# SerialChiller.net
KiCad netlist of a schematic drawn in EAGLE
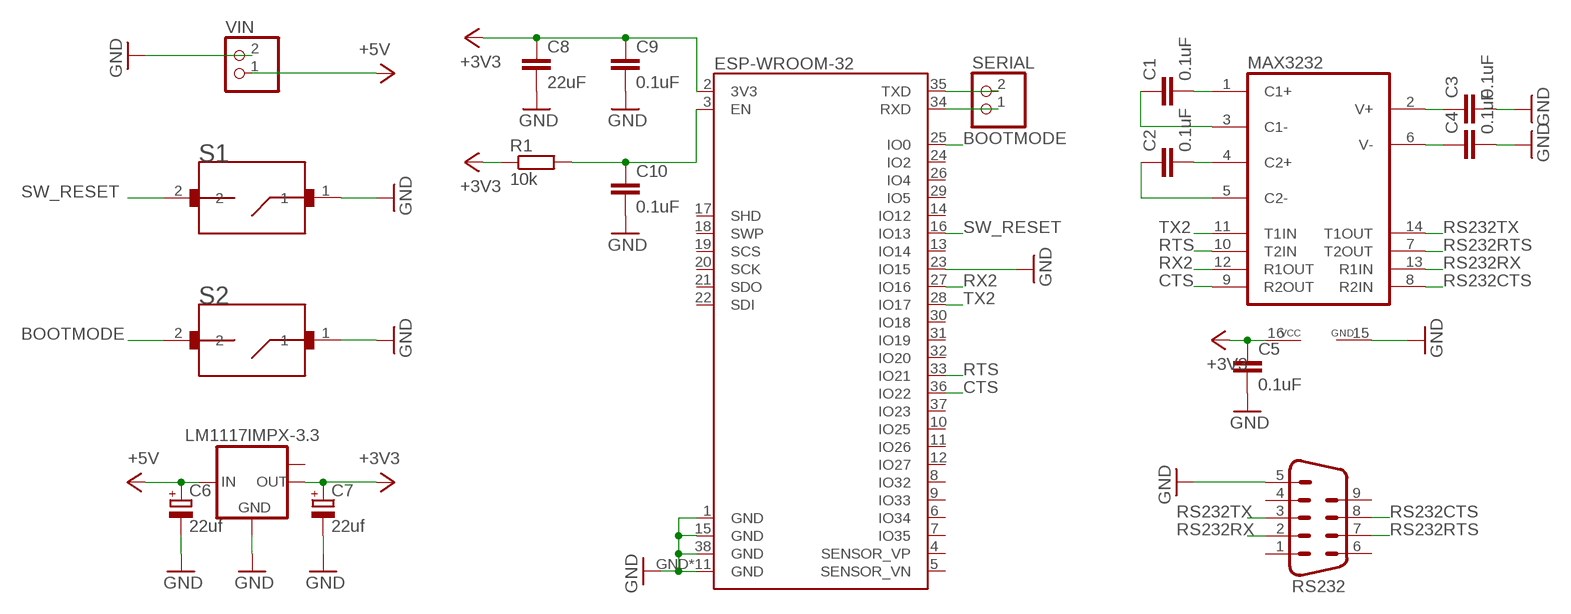
[diagram p0: schematic, sheet 1]

(export (version "E")
  (design (tool "Eeschema 10.0.6"))
  (components
    (comp (ref "C1")
      (value "0.1uF")
      (footprint "eagle-import:C0603")
      (libsource (lib "eagle-import") (part "C-EUC0603"))
    )
    (comp (ref "C2")
      (value "0.1uF")
      (footprint "eagle-import:C0603")
      (libsource (lib "eagle-import") (part "C-EUC0603"))
    )
    (comp (ref "C3")
      (value "0.1uF")
      (footprint "eagle-import:C0603")
      (libsource (lib "eagle-import") (part "C-EUC0603"))
    )
    (comp (ref "C4")
      (value "0.1uF")
      (footprint "eagle-import:C0603")
      (libsource (lib "eagle-import") (part "C-EUC0603"))
    )
    (comp (ref "C5")
      (value "0.1uF")
      (footprint "eagle-import:C0603")
      (libsource (lib "eagle-import") (part "C-EUC0603"))
    )
    (comp (ref "C6")
      (value "22uf")
      (footprint "eagle-import:A_3216-18R")
      (libsource (lib "eagle-import") (part "CPOL-EUA/3216-18R"))
    )
    (comp (ref "C7")
      (value "22uf")
      (footprint "eagle-import:A_3216-18R")
      (libsource (lib "eagle-import") (part "CPOL-EUA/3216-18R"))
    )
    (comp (ref "C8")
      (value "22uF")
      (footprint "eagle-import:C1206")
      (libsource (lib "eagle-import") (part "C-EUC1206"))
    )
    (comp (ref "C9")
      (value "0.1uF")
      (footprint "eagle-import:C0603")
      (libsource (lib "eagle-import") (part "C-EUC0603"))
    )
    (comp (ref "C10")
      (value "0.1uF")
      (footprint "eagle-import:C0603")
      (libsource (lib "eagle-import") (part "C-EUC0603"))
    )
    (comp (ref "ESP-WROOM-32")
      (value "ESP-WROOM-03")
      (footprint "eagle-import:ESP-WROOM-03")
      (libsource (lib "eagle-import") (part "ESP-WROOM-03"))
    )
    (comp (ref "IC1")
      (value "LM1117IMPX-3.3")
      (footprint "eagle-import:SOT223")
      (libsource (lib "eagle-import") (part "LM1117IMPX-3.3"))
    )
    (comp (ref "MAX3232")
      (value "MAX3232CSE")
      (footprint "eagle-import:SO16")
      (libsource (lib "eagle-import") (part "MAX3232SEC"))
    )
    (comp (ref "R1")
      (value "10k")
      (footprint "eagle-import:R0603")
      (libsource (lib "eagle-import") (part "R-EU_R0603"))
    )
    (comp (ref "RS232")
      (value "M09HP")
      (footprint "eagle-import:M09HP")
      (libsource (lib "eagle-import") (part "M09HP"))
    )
    (comp (ref "S1")
      (value "B3U-1000P")
      (footprint "eagle-import:SW_B3U-1000P")
      (fields (field (name "MF") "Omron"))
      (libsource (lib "eagle-import") (part "B3U-1000P"))
    )
    (comp (ref "S2")
      (value "B3U-1000P")
      (footprint "eagle-import:SW_B3U-1000P")
      (fields (field (name "MF") "Omron"))
      (libsource (lib "eagle-import") (part "B3U-1000P"))
    )
    (comp (ref "SERIAL")
      (value "Serial")
      (footprint "eagle-import:1X02")
      (libsource (lib "eagle-import") (part "PINHD-1X2"))
    )
    (comp (ref "VIN")
      (value "Power")
      (footprint "eagle-import:1X02")
      (libsource (lib "eagle-import") (part "PINHD-1X2"))
    )
  )
  (nets
    (net (code "1") (name "+3V3") (class "Default")
      (node (ref "C5") (pin "1") (pinfunction "1_1") (pintype "passive"))
      (node (ref "C7") (pin "+") (pinfunction "+_+") (pintype "passive"))
      (node (ref "C8") (pin "1") (pinfunction "1_1") (pintype "passive"))
      (node (ref "C9") (pin "1") (pinfunction "1_1") (pintype "passive"))
      (node (ref "ESP-WROOM-32") (pin "2") (pinfunction "3V3_2") (pintype "bidirectional"))
      (node (ref "IC1") (pin "2") (pinfunction "OUT_2") (pintype "passive"))
      (node (ref "MAX3232") (pin "16") (pinfunction "VCC_16") (pintype "power_in"))
      (node (ref "R1") (pin "1") (pinfunction "1_1") (pintype "passive"))
    )
    (net (code "2") (name "+5V") (class "Default")
      (node (ref "C6") (pin "+") (pinfunction "+_+") (pintype "passive"))
      (node (ref "IC1") (pin "3") (pinfunction "IN_3") (pintype "input"))
      (node (ref "VIN") (pin "1") (pinfunction "1_1") (pintype "passive"))
    )
    (net (code "3") (name "/BOOTMODE") (class "Default")
      (node (ref "ESP-WROOM-32") (pin "25") (pinfunction "IO0_25") (pintype "bidirectional"))
      (node (ref "S2") (pin "2") (pinfunction "2_2") (pintype "passive"))
    )
    (net (code "4") (name "/CTS") (class "Default")
      (node (ref "ESP-WROOM-32") (pin "36") (pinfunction "IO22_36") (pintype "bidirectional"))
      (node (ref "MAX3232") (pin "9") (pinfunction "R2OUT_9") (pintype "output"))
    )
    (net (code "5") (name "/RS232CTS") (class "Default")
      (node (ref "MAX3232") (pin "8") (pinfunction "R2IN_8") (pintype "input"))
      (node (ref "RS232") (pin "8") (pinfunction "8_8") (pintype "passive"))
    )
    (net (code "6") (name "/RS232RTS") (class "Default")
      (node (ref "MAX3232") (pin "7") (pinfunction "T2OUT_7") (pintype "output"))
      (node (ref "RS232") (pin "7") (pinfunction "7_7") (pintype "passive"))
    )
    (net (code "7") (name "/RS232RX") (class "Default")
      (node (ref "MAX3232") (pin "13") (pinfunction "R1IN_13") (pintype "input"))
      (node (ref "RS232") (pin "2") (pinfunction "2_2") (pintype "passive"))
    )
    (net (code "8") (name "/RS232TX") (class "Default")
      (node (ref "MAX3232") (pin "14") (pinfunction "T1OUT_14") (pintype "output"))
      (node (ref "RS232") (pin "3") (pinfunction "3_3") (pintype "passive"))
    )
    (net (code "9") (name "/RTS") (class "Default")
      (node (ref "ESP-WROOM-32") (pin "33") (pinfunction "IO21_33") (pintype "bidirectional"))
      (node (ref "MAX3232") (pin "10") (pinfunction "T2IN_10") (pintype "input"))
    )
    (net (code "10") (name "/RX2") (class "Default")
      (node (ref "ESP-WROOM-32") (pin "27") (pinfunction "IO16_27") (pintype "bidirectional"))
      (node (ref "MAX3232") (pin "12") (pinfunction "R1OUT_12") (pintype "output"))
    )
    (net (code "11") (name "/SW_RESET") (class "Default")
      (node (ref "ESP-WROOM-32") (pin "16") (pinfunction "IO13_16") (pintype "bidirectional"))
      (node (ref "S1") (pin "2") (pinfunction "2_2") (pintype "passive"))
    )
    (net (code "12") (name "/TX2") (class "Default")
      (node (ref "ESP-WROOM-32") (pin "28") (pinfunction "IO17_28") (pintype "bidirectional"))
      (node (ref "MAX3232") (pin "11") (pinfunction "T1IN_11") (pintype "input"))
    )
    (net (code "13") (name "GND") (class "Default")
      (node (ref "C10") (pin "2") (pinfunction "2_2") (pintype "passive"))
      (node (ref "C3") (pin "2") (pinfunction "2_2") (pintype "passive"))
      (node (ref "C4") (pin "2") (pinfunction "2_2") (pintype "passive"))
      (node (ref "C5") (pin "2") (pinfunction "2_2") (pintype "passive"))
      (node (ref "C6") (pin "-") (pinfunction "-_-") (pintype "passive"))
      (node (ref "C7") (pin "-") (pinfunction "-_-") (pintype "passive"))
      (node (ref "C8") (pin "2") (pinfunction "2_2") (pintype "passive"))
      (node (ref "C9") (pin "2") (pinfunction "2_2") (pintype "passive"))
      (node (ref "ESP-WROOM-32") (pin "1") (pinfunction "GND_1") (pintype "bidirectional"))
      (node (ref "ESP-WROOM-32") (pin "15") (pinfunction "GND_15") (pintype "bidirectional"))
      (node (ref "ESP-WROOM-32") (pin "23") (pinfunction "IO15_23") (pintype "bidirectional"))
      (node (ref "ESP-WROOM-32") (pin "38") (pinfunction "GND_38") (pintype "bidirectional"))
      (node (ref "ESP-WROOM-32") (pin "GND") (pinfunction "GND_GND") (pintype "bidirectional"))
      (node (ref "ESP-WROOM-32") (pin "GND1") (pinfunction "GND_GND1") (pintype "bidirectional"))
      (node (ref "ESP-WROOM-32") (pin "P$1") (pinfunction "GND_P$1") (pintype "bidirectional"))
      (node (ref "ESP-WROOM-32") (pin "P$2") (pinfunction "GND_P$2") (pintype "bidirectional"))
      (node (ref "ESP-WROOM-32") (pin "P$3") (pinfunction "GND_P$3") (pintype "bidirectional"))
      (node (ref "ESP-WROOM-32") (pin "P$4") (pinfunction "GND_P$4") (pintype "bidirectional"))
      (node (ref "ESP-WROOM-32") (pin "P$5") (pinfunction "GND_P$5") (pintype "bidirectional"))
      (node (ref "ESP-WROOM-32") (pin "P$6") (pinfunction "GND_P$6") (pintype "bidirectional"))
      (node (ref "ESP-WROOM-32") (pin "P$7") (pinfunction "GND_P$7") (pintype "bidirectional"))
      (node (ref "ESP-WROOM-32") (pin "P$8") (pinfunction "GND_P$8") (pintype "bidirectional"))
      (node (ref "ESP-WROOM-32") (pin "P$9") (pinfunction "GND_P$9") (pintype "bidirectional"))
      (node (ref "IC1") (pin "1") (pinfunction "GND_1") (pintype "input"))
      (node (ref "MAX3232") (pin "15") (pinfunction "GND_15") (pintype "power_in"))
      (node (ref "RS232") (pin "5") (pinfunction "5_5") (pintype "passive"))
      (node (ref "S1") (pin "1") (pinfunction "1_1") (pintype "passive"))
      (node (ref "S2") (pin "1") (pinfunction "1_1") (pintype "passive"))
      (node (ref "VIN") (pin "2") (pinfunction "2_2") (pintype "passive"))
    )
    (net (code "14") (name "Net-(ESP-WROOM-32-EN)") (class "Default")
      (node (ref "C10") (pin "1") (pinfunction "1_1") (pintype "passive"))
      (node (ref "ESP-WROOM-32") (pin "3") (pinfunction "EN_3") (pintype "bidirectional"))
      (node (ref "R1") (pin "2") (pinfunction "2_2") (pintype "passive"))
    )
    (net (code "15") (name "Net-(ESP-WROOM-32-RXD)") (class "Default")
      (node (ref "ESP-WROOM-32") (pin "34") (pinfunction "RXD_34") (pintype "bidirectional"))
      (node (ref "SERIAL") (pin "1") (pinfunction "1_1") (pintype "passive"))
    )
    (net (code "16") (name "Net-(ESP-WROOM-32-TXD)") (class "Default")
      (node (ref "ESP-WROOM-32") (pin "35") (pinfunction "TXD_35") (pintype "bidirectional"))
      (node (ref "SERIAL") (pin "2") (pinfunction "2_2") (pintype "passive"))
    )
    (net (code "17") (name "Net-(MAX3232A-C1+)") (class "Default")
      (node (ref "C1") (pin "2") (pinfunction "2_2") (pintype "passive"))
      (node (ref "MAX3232") (pin "1") (pinfunction "C1+_1") (pintype "bidirectional"))
    )
    (net (code "18") (name "Net-(MAX3232A-C1-)") (class "Default")
      (node (ref "C1") (pin "1") (pinfunction "1_1") (pintype "passive"))
      (node (ref "MAX3232") (pin "3") (pinfunction "C1-_3") (pintype "bidirectional"))
    )
    (net (code "19") (name "Net-(MAX3232A-C2+)") (class "Default")
      (node (ref "C2") (pin "2") (pinfunction "2_2") (pintype "passive"))
      (node (ref "MAX3232") (pin "4") (pinfunction "C2+_4") (pintype "bidirectional"))
    )
    (net (code "20") (name "Net-(MAX3232A-C2-)") (class "Default")
      (node (ref "C2") (pin "1") (pinfunction "1_1") (pintype "passive"))
      (node (ref "MAX3232") (pin "5") (pinfunction "C2-_5") (pintype "bidirectional"))
    )
    (net (code "21") (name "Net-(MAX3232A-V+)") (class "Default")
      (node (ref "C3") (pin "1") (pinfunction "1_1") (pintype "passive"))
      (node (ref "MAX3232") (pin "2") (pinfunction "V+_2") (pintype "bidirectional"))
    )
    (net (code "22") (name "Net-(MAX3232A-V-)") (class "Default")
      (node (ref "C4") (pin "1") (pinfunction "1_1") (pintype "passive"))
      (node (ref "MAX3232") (pin "6") (pinfunction "V-_6") (pintype "bidirectional"))
    )
    (net (code "23") (name "unconnected-(ESP-WROOM-32-IO2-Pad24)") (class "Default")
      (node (ref "ESP-WROOM-32") (pin "24") (pinfunction "IO2_24") (pintype "bidirectional"))
    )
    (net (code "24") (name "unconnected-(ESP-WROOM-32-IO4-Pad26)") (class "Default")
      (node (ref "ESP-WROOM-32") (pin "26") (pinfunction "IO4_26") (pintype "bidirectional"))
    )
    (net (code "25") (name "unconnected-(ESP-WROOM-32-IO5-Pad29)") (class "Default")
      (node (ref "ESP-WROOM-32") (pin "29") (pinfunction "IO5_29") (pintype "bidirectional"))
    )
    (net (code "26") (name "unconnected-(ESP-WROOM-32-IO12-Pad14)") (class "Default")
      (node (ref "ESP-WROOM-32") (pin "14") (pinfunction "IO12_14") (pintype "bidirectional"))
    )
    (net (code "27") (name "unconnected-(ESP-WROOM-32-IO14-Pad13)") (class "Default")
      (node (ref "ESP-WROOM-32") (pin "13") (pinfunction "IO14_13") (pintype "bidirectional"))
    )
    (net (code "28") (name "unconnected-(ESP-WROOM-32-IO18-Pad30)") (class "Default")
      (node (ref "ESP-WROOM-32") (pin "30") (pinfunction "IO18_30") (pintype "bidirectional"))
    )
    (net (code "29") (name "unconnected-(ESP-WROOM-32-IO19-Pad31)") (class "Default")
      (node (ref "ESP-WROOM-32") (pin "31") (pinfunction "IO19_31") (pintype "bidirectional"))
    )
    (net (code "30") (name "unconnected-(ESP-WROOM-32-IO20-Pad32)") (class "Default")
      (node (ref "ESP-WROOM-32") (pin "32") (pinfunction "IO20_32") (pintype "bidirectional"))
    )
    (net (code "31") (name "unconnected-(ESP-WROOM-32-IO23-Pad37)") (class "Default")
      (node (ref "ESP-WROOM-32") (pin "37") (pinfunction "IO23_37") (pintype "bidirectional"))
    )
    (net (code "32") (name "unconnected-(ESP-WROOM-32-IO25-Pad10)") (class "Default")
      (node (ref "ESP-WROOM-32") (pin "10") (pinfunction "IO25_10") (pintype "bidirectional"))
    )
    (net (code "33") (name "unconnected-(ESP-WROOM-32-IO26-Pad11)") (class "Default")
      (node (ref "ESP-WROOM-32") (pin "11") (pinfunction "IO26_11") (pintype "bidirectional"))
    )
    (net (code "34") (name "unconnected-(ESP-WROOM-32-IO27-Pad12)") (class "Default")
      (node (ref "ESP-WROOM-32") (pin "12") (pinfunction "IO27_12") (pintype "bidirectional"))
    )
    (net (code "35") (name "unconnected-(ESP-WROOM-32-IO32-Pad8)") (class "Default")
      (node (ref "ESP-WROOM-32") (pin "8") (pinfunction "IO32_8") (pintype "bidirectional"))
    )
    (net (code "36") (name "unconnected-(ESP-WROOM-32-IO33-Pad9)") (class "Default")
      (node (ref "ESP-WROOM-32") (pin "9") (pinfunction "IO33_9") (pintype "bidirectional"))
    )
    (net (code "37") (name "unconnected-(ESP-WROOM-32-IO34-Pad6)") (class "Default")
      (node (ref "ESP-WROOM-32") (pin "6") (pinfunction "IO34_6") (pintype "bidirectional"))
    )
    (net (code "38") (name "unconnected-(ESP-WROOM-32-IO35-Pad7)") (class "Default")
      (node (ref "ESP-WROOM-32") (pin "7") (pinfunction "IO35_7") (pintype "bidirectional"))
    )
    (net (code "39") (name "unconnected-(ESP-WROOM-32-SCK-Pad20)") (class "Default")
      (node (ref "ESP-WROOM-32") (pin "20") (pinfunction "SCK_20") (pintype "bidirectional"))
    )
    (net (code "40") (name "unconnected-(ESP-WROOM-32-SCS-Pad19)") (class "Default")
      (node (ref "ESP-WROOM-32") (pin "19") (pinfunction "SCS_19") (pintype "bidirectional"))
    )
    (net (code "41") (name "unconnected-(ESP-WROOM-32-SDI-Pad22)") (class "Default")
      (node (ref "ESP-WROOM-32") (pin "22") (pinfunction "SDI_22") (pintype "bidirectional"))
    )
    (net (code "42") (name "unconnected-(ESP-WROOM-32-SDO-Pad21)") (class "Default")
      (node (ref "ESP-WROOM-32") (pin "21") (pinfunction "SDO_21") (pintype "bidirectional"))
    )
    (net (code "43") (name "unconnected-(ESP-WROOM-32-SENSOR_VN-Pad5)") (class "Default")
      (node (ref "ESP-WROOM-32") (pin "5") (pinfunction "SENSOR_VN_5") (pintype "bidirectional"))
    )
    (net (code "44") (name "unconnected-(ESP-WROOM-32-SENSOR_VP-Pad4)") (class "Default")
      (node (ref "ESP-WROOM-32") (pin "4") (pinfunction "SENSOR_VP_4") (pintype "bidirectional"))
    )
    (net (code "45") (name "unconnected-(ESP-WROOM-32-SHD-Pad17)") (class "Default")
      (node (ref "ESP-WROOM-32") (pin "17") (pinfunction "SHD_17") (pintype "bidirectional"))
    )
    (net (code "46") (name "unconnected-(ESP-WROOM-32-SWP-Pad18)") (class "Default")
      (node (ref "ESP-WROOM-32") (pin "18") (pinfunction "SWP_18") (pintype "bidirectional"))
    )
    (net (code "47") (name "unconnected-(IC1-OUT1-PadTAB)") (class "Default")
      (node (ref "IC1") (pin "TAB") (pinfunction "OUT1_TAB") (pintype "passive"))
    )
    (net (code "48") (name "unconnected-(RS232-Pad1)") (class "Default")
      (node (ref "RS232") (pin "1") (pinfunction "1_1") (pintype "passive"))
    )
    (net (code "49") (name "unconnected-(RS232-Pad4)") (class "Default")
      (node (ref "RS232") (pin "4") (pinfunction "4_4") (pintype "passive"))
    )
    (net (code "50") (name "unconnected-(RS232-Pad6)") (class "Default")
      (node (ref "RS232") (pin "6") (pinfunction "6_6") (pintype "passive"))
    )
    (net (code "51") (name "unconnected-(RS232-Pad9)") (class "Default")
      (node (ref "RS232") (pin "9") (pinfunction "9_9") (pintype "passive"))
    )
  )
)
